# OutputBoard.net
KiCad netlist of a schematic drawn in Altium Designer
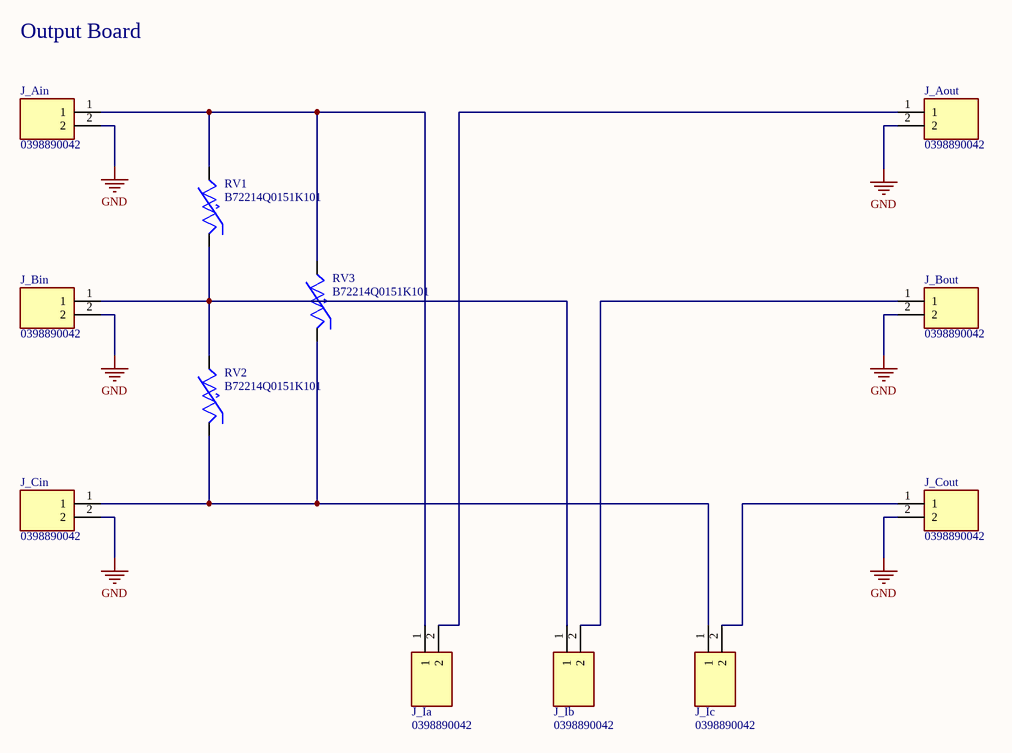
[diagram p0: OutputBoard.SchDoc]

(export (version "E")
  (design (tool "Eeschema 10.0.6"))
  (components
    (comp (ref "J_Ain")
      (value "0398890042")
      (footprint "0398890042")
      (description "Conn Eurostyle Block 2 POS 5.08mm Solder ST Thru-Hole 17.5A/Contact")
      (libsource (lib "") (part "0398890042_2"))
    )
    (comp (ref "J_Aout")
      (value "0398890042")
      (footprint "0398890042")
      (description "Conn Eurostyle Block 2 POS 5.08mm Solder ST Thru-Hole 17.5A/Contact")
      (libsource (lib "") (part "0398890042_1"))
    )
    (comp (ref "J_Bin")
      (value "0398890042")
      (footprint "0398890042")
      (description "Conn Eurostyle Block 2 POS 5.08mm Solder ST Thru-Hole 17.5A/Contact")
      (libsource (lib "") (part "0398890042_2"))
    )
    (comp (ref "J_Bout")
      (value "0398890042")
      (footprint "0398890042")
      (description "Conn Eurostyle Block 2 POS 5.08mm Solder ST Thru-Hole 17.5A/Contact")
      (libsource (lib "") (part "0398890042_1"))
    )
    (comp (ref "J_Cin")
      (value "0398890042")
      (footprint "0398890042")
      (description "Conn Eurostyle Block 2 POS 5.08mm Solder ST Thru-Hole 17.5A/Contact")
      (libsource (lib "") (part "0398890042_2"))
    )
    (comp (ref "J_Cout")
      (value "0398890042")
      (footprint "0398890042")
      (description "Conn Eurostyle Block 2 POS 5.08mm Solder ST Thru-Hole 17.5A/Contact")
      (libsource (lib "") (part "0398890042_1"))
    )
    (comp (ref "J_Ia")
      (value "0398890042")
      (footprint "0398890042")
      (description "Conn Eurostyle Block 2 POS 5.08mm Solder ST Thru-Hole 17.5A/Contact")
      (libsource (lib "0398890042") (part "0398890042"))
    )
    (comp (ref "J_Ib")
      (value "0398890042")
      (footprint "0398890042")
      (description "Conn Eurostyle Block 2 POS 5.08mm Solder ST Thru-Hole 17.5A/Contact")
      (libsource (lib "0398890042") (part "0398890042"))
    )
    (comp (ref "J_Ic")
      (value "0398890042")
      (footprint "0398890042")
      (description "Conn Eurostyle Block 2 POS 5.08mm Solder ST Thru-Hole 17.5A/Contact")
      (libsource (lib "0398890042") (part "0398890042"))
    )
    (comp (ref "RV1")
      (value "B72214Q0151K101")
      (footprint "VAR_B72214Q0151K101")
      (description "240 V 8 kA Varistor 1 Circuit Through Hole Radial")
      (fields (field (name "MF") "EPCOS"))
      (libsource (lib "B72214Q0151K101") (part "B72214Q0151K101"))
    )
    (comp (ref "RV2")
      (value "B72214Q0151K101")
      (footprint "VAR_B72214Q0151K101")
      (description "240 V 8 kA Varistor 1 Circuit Through Hole Radial")
      (fields (field (name "MF") "EPCOS"))
      (libsource (lib "B72214Q0151K101") (part "B72214Q0151K101"))
    )
    (comp (ref "RV3")
      (value "B72214Q0151K101")
      (footprint "VAR_B72214Q0151K101")
      (description "240 V 8 kA Varistor 1 Circuit Through Hole Radial")
      (fields (field (name "MF") "EPCOS"))
      (libsource (lib "B72214Q0151K101") (part "B72214Q0151K101"))
    )
  )
  (nets
    (net (code "1") (name "GND") (class "Default")
      (node (ref "J_Ain") (pin "2") (pinfunction "2_2") (pintype "passive"))
      (node (ref "J_Aout") (pin "2") (pinfunction "2_2") (pintype "passive"))
      (node (ref "J_Bin") (pin "2") (pinfunction "2_2") (pintype "passive"))
      (node (ref "J_Bout") (pin "2") (pinfunction "2_2") (pintype "passive"))
      (node (ref "J_Cin") (pin "2") (pinfunction "2_2") (pintype "passive"))
      (node (ref "J_Cout") (pin "2") (pinfunction "2_2") (pintype "passive"))
    )
    (net (code "2") (name "Net-(J_Ain-Pad1)") (class "Default")
      (node (ref "J_Ain") (pin "1") (pinfunction "1_1") (pintype "passive"))
      (node (ref "J_Ia") (pin "1") (pinfunction "1_1") (pintype "passive"))
      (node (ref "RV1") (pin "2") (pinfunction "2_2") (pintype "passive"))
      (node (ref "RV3") (pin "2") (pinfunction "2_2") (pintype "passive"))
    )
    (net (code "3") (name "Net-(J_Aout-Pad1)") (class "Default")
      (node (ref "J_Aout") (pin "1") (pinfunction "1_1") (pintype "passive"))
      (node (ref "J_Ia") (pin "2") (pinfunction "2_2") (pintype "passive"))
    )
    (net (code "4") (name "Net-(J_Bin-Pad1)") (class "Default")
      (node (ref "J_Bin") (pin "1") (pinfunction "1_1") (pintype "passive"))
      (node (ref "J_Ib") (pin "1") (pinfunction "1_1") (pintype "passive"))
      (node (ref "RV1") (pin "1") (pinfunction "1_1") (pintype "passive"))
      (node (ref "RV2") (pin "2") (pinfunction "2_2") (pintype "passive"))
    )
    (net (code "5") (name "Net-(J_Bout-Pad1)") (class "Default")
      (node (ref "J_Bout") (pin "1") (pinfunction "1_1") (pintype "passive"))
      (node (ref "J_Ib") (pin "2") (pinfunction "2_2") (pintype "passive"))
    )
    (net (code "6") (name "Net-(J_Cin-Pad1)") (class "Default")
      (node (ref "J_Cin") (pin "1") (pinfunction "1_1") (pintype "passive"))
      (node (ref "J_Ic") (pin "1") (pinfunction "1_1") (pintype "passive"))
      (node (ref "RV2") (pin "1") (pinfunction "1_1") (pintype "passive"))
      (node (ref "RV3") (pin "1") (pinfunction "1_1") (pintype "passive"))
    )
    (net (code "7") (name "Net-(J_Cout-Pad1)") (class "Default")
      (node (ref "J_Cout") (pin "1") (pinfunction "1_1") (pintype "passive"))
      (node (ref "J_Ic") (pin "2") (pinfunction "2_2") (pintype "passive"))
    )
  )
)
